# 6502_cable_ada.net
KiCad netlist of a schematic drawn in EAGLE
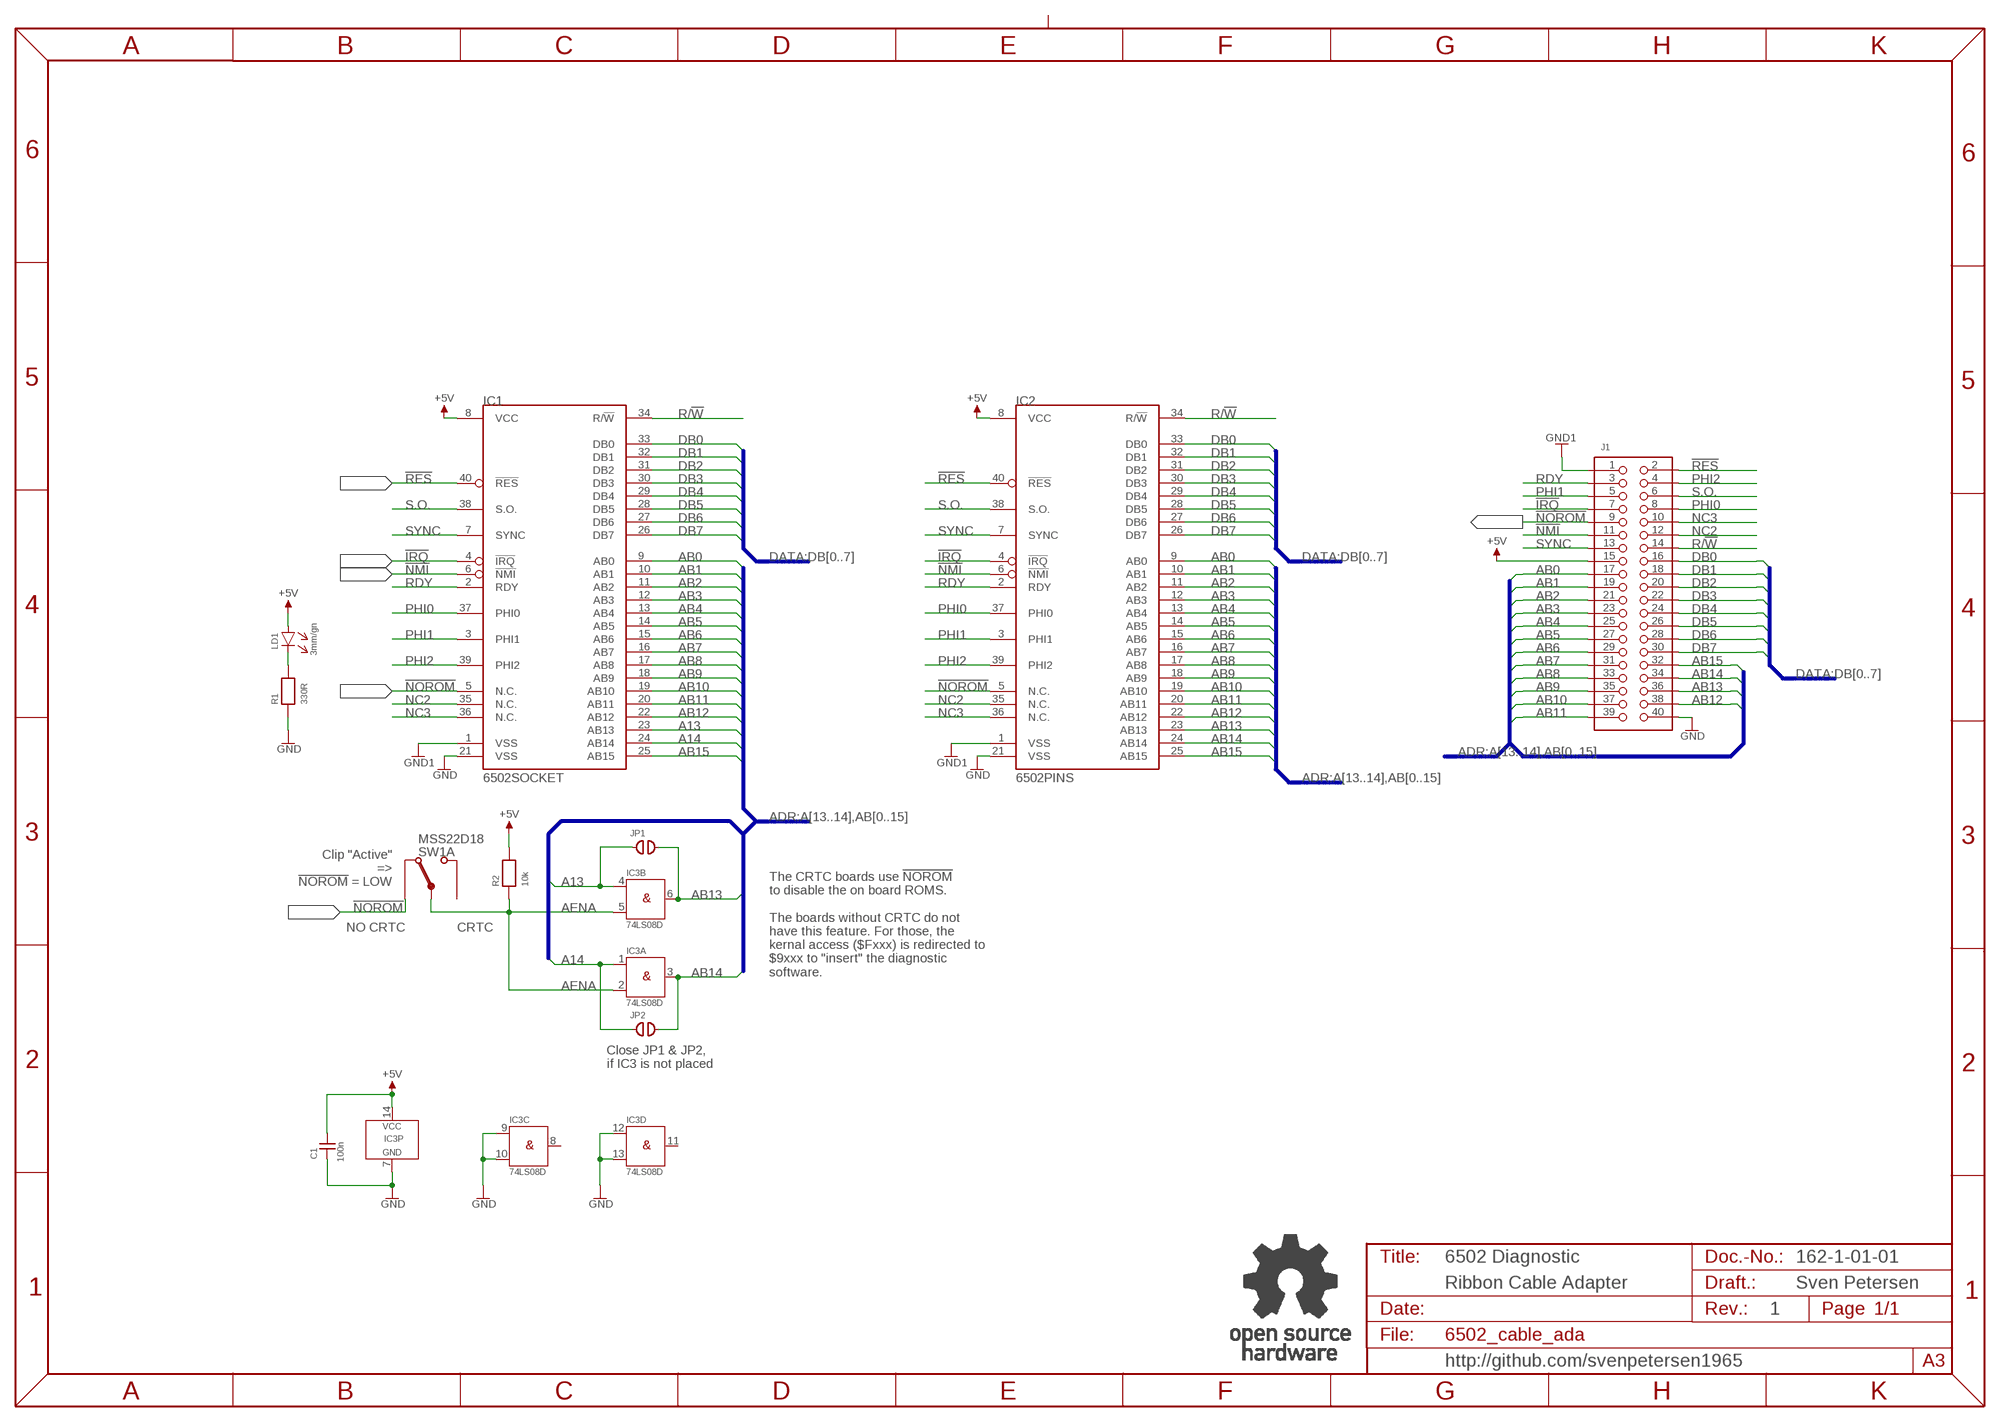
[diagram p0: schematic, sheet 1]

(export (version "E")
  (design (tool "Eeschema 10.0.6"))
  (components
    (comp (ref "C1")
      (value "100n")
      (footprint "eagle-import:0805")
      (libsource (lib "eagle-import") (part "C-0805"))
    )
    (comp (ref "IC1")
      (value "6502SOCKET")
      (footprint "eagle-import:GS40P")
      (libsource (lib "eagle-import") (part "6502SOCKET"))
    )
    (comp (ref "IC2")
      (value "6502PINS")
      (footprint "eagle-import:DIL40_PINS_SS")
      (libsource (lib "eagle-import") (part "6502PINS"))
    )
    (comp (ref "IC3")
      (value "74LS08D")
      (footprint "eagle-import:SO-14")
      (libsource (lib "eagle-import") (part "7408HC"))
    )
    (comp (ref "J1")
      (value "PINHD-2X20WV")
      (footprint "eagle-import:2X20WV")
      (libsource (lib "eagle-import") (part "PINHD-2X20WV"))
    )
    (comp (ref "JP1")
      (value "OPEN")
      (footprint "eagle-import:CP_OP")
      (libsource (lib "eagle-import") (part "OPEN"))
    )
    (comp (ref "JP2")
      (value "OPEN")
      (footprint "eagle-import:CP_OP")
      (libsource (lib "eagle-import") (part "OPEN"))
    )
    (comp (ref "LD1")
      (value "3mm/gn")
      (footprint "eagle-import:3MM")
      (libsource (lib "eagle-import") (part "3MM"))
    )
    (comp (ref "R1")
      (value "330R")
      (footprint "eagle-import:0805")
      (libsource (lib "eagle-import") (part "RES040805"))
    )
    (comp (ref "R2")
      (value "10k")
      (footprint "eagle-import:0805")
      (libsource (lib "eagle-import") (part "RES040805"))
    )
    (comp (ref "SW1")
      (value "MSS22D18")
      (footprint "eagle-import:DPDT_9MM")
      (libsource (lib "eagle-import") (part "DPDT_9MM"))
    )
    (comp (ref "U$11")
      (value "OPEN_SOURCE_HW")
      (footprint "eagle-import:OPENHW")
      (libsource (lib "eagle-import") (part "OPEN_SOURCE_HW"))
    )
  )
  (nets
    (net (code "9") (name "+5V") (class "Default")
      (node (ref "C1") (pin "2") (pinfunction "2_2") (pintype "passive"))
      (node (ref "IC1") (pin "8") (pinfunction "VCC_8") (pintype "power_in"))
      (node (ref "IC2") (pin "8") (pinfunction "VCC_8") (pintype "power_in"))
      (node (ref "IC3") (pin "14") (pinfunction "VCC_14") (pintype "bidirectional"))
      (node (ref "J1") (pin "15") (pinfunction "15_15") (pintype "passive"))
      (node (ref "LD1") (pin "A") (pinfunction "A_A") (pintype "bidirectional"))
      (node (ref "R2") (pin "2") (pinfunction "2_2") (pintype "passive"))
    )
    (net (code "10") (name "/A13") (class "Default")
      (node (ref "IC1") (pin "23") (pinfunction "AB13_23") (pintype "output"))
      (node (ref "IC3") (pin "4") (pinfunction "I0_4") (pintype "input"))
      (node (ref "JP1") (pin "1") (pinfunction "1_1") (pintype "passive"))
    )
    (net (code "11") (name "/A14") (class "Default")
      (node (ref "IC1") (pin "24") (pinfunction "AB14_24") (pintype "output"))
      (node (ref "IC3") (pin "1") (pinfunction "I0_1") (pintype "input"))
      (node (ref "JP2") (pin "1") (pinfunction "1_1") (pintype "passive"))
    )
    (net (code "12") (name "/AB0") (class "Default")
      (node (ref "IC1") (pin "9") (pinfunction "AB0_9") (pintype "output"))
      (node (ref "IC2") (pin "9") (pinfunction "AB0_9") (pintype "output"))
      (node (ref "J1") (pin "17") (pinfunction "17_17") (pintype "passive"))
    )
    (net (code "13") (name "/AB1") (class "Default")
      (node (ref "IC1") (pin "10") (pinfunction "AB1_10") (pintype "output"))
      (node (ref "IC2") (pin "10") (pinfunction "AB1_10") (pintype "output"))
      (node (ref "J1") (pin "19") (pinfunction "19_19") (pintype "passive"))
    )
    (net (code "14") (name "/AB2") (class "Default")
      (node (ref "IC1") (pin "11") (pinfunction "AB2_11") (pintype "output"))
      (node (ref "IC2") (pin "11") (pinfunction "AB2_11") (pintype "output"))
      (node (ref "J1") (pin "21") (pinfunction "21_21") (pintype "passive"))
    )
    (net (code "15") (name "/AB3") (class "Default")
      (node (ref "IC1") (pin "12") (pinfunction "AB3_12") (pintype "output"))
      (node (ref "IC2") (pin "12") (pinfunction "AB3_12") (pintype "output"))
      (node (ref "J1") (pin "23") (pinfunction "23_23") (pintype "passive"))
    )
    (net (code "16") (name "/AB4") (class "Default")
      (node (ref "IC1") (pin "13") (pinfunction "AB4_13") (pintype "output"))
      (node (ref "IC2") (pin "13") (pinfunction "AB4_13") (pintype "output"))
      (node (ref "J1") (pin "25") (pinfunction "25_25") (pintype "passive"))
    )
    (net (code "17") (name "/AB5") (class "Default")
      (node (ref "IC1") (pin "14") (pinfunction "AB5_14") (pintype "output"))
      (node (ref "IC2") (pin "14") (pinfunction "AB5_14") (pintype "output"))
      (node (ref "J1") (pin "27") (pinfunction "27_27") (pintype "passive"))
    )
    (net (code "18") (name "/AB6") (class "Default")
      (node (ref "IC1") (pin "15") (pinfunction "AB6_15") (pintype "output"))
      (node (ref "IC2") (pin "15") (pinfunction "AB6_15") (pintype "output"))
      (node (ref "J1") (pin "29") (pinfunction "29_29") (pintype "passive"))
    )
    (net (code "19") (name "/AB7") (class "Default")
      (node (ref "IC1") (pin "16") (pinfunction "AB7_16") (pintype "output"))
      (node (ref "IC2") (pin "16") (pinfunction "AB7_16") (pintype "output"))
      (node (ref "J1") (pin "31") (pinfunction "31_31") (pintype "passive"))
    )
    (net (code "20") (name "/AB8") (class "Default")
      (node (ref "IC1") (pin "17") (pinfunction "AB8_17") (pintype "output"))
      (node (ref "IC2") (pin "17") (pinfunction "AB8_17") (pintype "output"))
      (node (ref "J1") (pin "33") (pinfunction "33_33") (pintype "passive"))
    )
    (net (code "21") (name "/AB9") (class "Default")
      (node (ref "IC1") (pin "18") (pinfunction "AB9_18") (pintype "output"))
      (node (ref "IC2") (pin "18") (pinfunction "AB9_18") (pintype "output"))
      (node (ref "J1") (pin "35") (pinfunction "35_35") (pintype "passive"))
    )
    (net (code "22") (name "/AB10") (class "Default")
      (node (ref "IC1") (pin "19") (pinfunction "AB10_19") (pintype "output"))
      (node (ref "IC2") (pin "19") (pinfunction "AB10_19") (pintype "output"))
      (node (ref "J1") (pin "37") (pinfunction "37_37") (pintype "passive"))
    )
    (net (code "23") (name "/AB11") (class "Default")
      (node (ref "IC1") (pin "20") (pinfunction "AB11_20") (pintype "output"))
      (node (ref "IC2") (pin "20") (pinfunction "AB11_20") (pintype "output"))
      (node (ref "J1") (pin "39") (pinfunction "39_39") (pintype "passive"))
    )
    (net (code "24") (name "/AB12") (class "Default")
      (node (ref "IC1") (pin "22") (pinfunction "AB12_22") (pintype "output"))
      (node (ref "IC2") (pin "22") (pinfunction "AB12_22") (pintype "output"))
      (node (ref "J1") (pin "38") (pinfunction "38_38") (pintype "passive"))
    )
    (net (code "25") (name "/AB13") (class "Default")
      (node (ref "IC2") (pin "23") (pinfunction "AB13_23") (pintype "output"))
      (node (ref "IC3") (pin "6") (pinfunction "O_6") (pintype "output"))
      (node (ref "J1") (pin "36") (pinfunction "36_36") (pintype "passive"))
      (node (ref "JP1") (pin "2") (pinfunction "2_2") (pintype "passive"))
    )
    (net (code "26") (name "/AB14") (class "Default")
      (node (ref "IC2") (pin "24") (pinfunction "AB14_24") (pintype "output"))
      (node (ref "IC3") (pin "3") (pinfunction "O_3") (pintype "output"))
      (node (ref "J1") (pin "34") (pinfunction "34_34") (pintype "passive"))
      (node (ref "JP2") (pin "2") (pinfunction "2_2") (pintype "passive"))
    )
    (net (code "27") (name "/AB15") (class "Default")
      (node (ref "IC1") (pin "25") (pinfunction "AB15_25") (pintype "output"))
      (node (ref "IC2") (pin "25") (pinfunction "AB15_25") (pintype "output"))
      (node (ref "J1") (pin "32") (pinfunction "32_32") (pintype "passive"))
    )
    (net (code "28") (name "/AENA") (class "Default")
      (node (ref "IC3") (pin "2") (pinfunction "I1_2") (pintype "input"))
      (node (ref "IC3") (pin "5") (pinfunction "I1_5") (pintype "input"))
      (node (ref "R2") (pin "1") (pinfunction "1_1") (pintype "passive"))
      (node (ref "SW1") (pin "2") (pinfunction "COM_2") (pintype "bidirectional"))
    )
    (net (code "30") (name "/DB0") (class "Default")
      (node (ref "IC1") (pin "33") (pinfunction "DB0_33") (pintype "bidirectional"))
      (node (ref "IC2") (pin "33") (pinfunction "DB0_33") (pintype "bidirectional"))
      (node (ref "J1") (pin "16") (pinfunction "16_16") (pintype "passive"))
    )
    (net (code "31") (name "/DB1") (class "Default")
      (node (ref "IC1") (pin "32") (pinfunction "DB1_32") (pintype "bidirectional"))
      (node (ref "IC2") (pin "32") (pinfunction "DB1_32") (pintype "bidirectional"))
      (node (ref "J1") (pin "18") (pinfunction "18_18") (pintype "passive"))
    )
    (net (code "32") (name "/DB2") (class "Default")
      (node (ref "IC1") (pin "31") (pinfunction "DB2_31") (pintype "bidirectional"))
      (node (ref "IC2") (pin "31") (pinfunction "DB2_31") (pintype "bidirectional"))
      (node (ref "J1") (pin "20") (pinfunction "20_20") (pintype "passive"))
    )
    (net (code "33") (name "/DB3") (class "Default")
      (node (ref "IC1") (pin "30") (pinfunction "DB3_30") (pintype "bidirectional"))
      (node (ref "IC2") (pin "30") (pinfunction "DB3_30") (pintype "bidirectional"))
      (node (ref "J1") (pin "22") (pinfunction "22_22") (pintype "passive"))
    )
    (net (code "34") (name "/DB4") (class "Default")
      (node (ref "IC1") (pin "29") (pinfunction "DB4_29") (pintype "bidirectional"))
      (node (ref "IC2") (pin "29") (pinfunction "DB4_29") (pintype "bidirectional"))
      (node (ref "J1") (pin "24") (pinfunction "24_24") (pintype "passive"))
    )
    (net (code "35") (name "/DB5") (class "Default")
      (node (ref "IC1") (pin "28") (pinfunction "DB5_28") (pintype "bidirectional"))
      (node (ref "IC2") (pin "28") (pinfunction "DB5_28") (pintype "bidirectional"))
      (node (ref "J1") (pin "26") (pinfunction "26_26") (pintype "passive"))
    )
    (net (code "36") (name "/DB6") (class "Default")
      (node (ref "IC1") (pin "27") (pinfunction "DB6_27") (pintype "bidirectional"))
      (node (ref "IC2") (pin "27") (pinfunction "DB6_27") (pintype "bidirectional"))
      (node (ref "J1") (pin "28") (pinfunction "28_28") (pintype "passive"))
    )
    (net (code "37") (name "/DB7") (class "Default")
      (node (ref "IC1") (pin "26") (pinfunction "DB7_26") (pintype "bidirectional"))
      (node (ref "IC2") (pin "26") (pinfunction "DB7_26") (pintype "bidirectional"))
      (node (ref "J1") (pin "30") (pinfunction "30_30") (pintype "passive"))
    )
    (net (code "38") (name "/NC2") (class "Default")
      (node (ref "IC1") (pin "35") (pinfunction "N.C._35") (pintype "passive"))
      (node (ref "IC2") (pin "35") (pinfunction "N.C._35") (pintype "passive"))
      (node (ref "J1") (pin "12") (pinfunction "12_12") (pintype "passive"))
    )
    (net (code "39") (name "/NC3") (class "Default")
      (node (ref "IC1") (pin "36") (pinfunction "N.C._36") (pintype "passive"))
      (node (ref "IC2") (pin "36") (pinfunction "N.C._36") (pintype "passive"))
      (node (ref "J1") (pin "10") (pinfunction "10_10") (pintype "passive"))
    )
    (net (code "40") (name "/PHI0") (class "Default")
      (node (ref "IC1") (pin "37") (pinfunction "PHI0_37") (pintype "input"))
      (node (ref "IC2") (pin "37") (pinfunction "PHI0_37") (pintype "input"))
      (node (ref "J1") (pin "8") (pinfunction "8_8") (pintype "passive"))
    )
    (net (code "41") (name "/PHI1") (class "Default")
      (node (ref "IC1") (pin "3") (pinfunction "PHI1_3") (pintype "output"))
      (node (ref "IC2") (pin "3") (pinfunction "PHI1_3") (pintype "output"))
      (node (ref "J1") (pin "5") (pinfunction "5_5") (pintype "passive"))
    )
    (net (code "42") (name "/PHI2") (class "Default")
      (node (ref "IC1") (pin "39") (pinfunction "PHI2_39") (pintype "output"))
      (node (ref "IC2") (pin "39") (pinfunction "PHI2_39") (pintype "output"))
      (node (ref "J1") (pin "4") (pinfunction "4_4") (pintype "passive"))
    )
    (net (code "43") (name "/RDY") (class "Default")
      (node (ref "IC1") (pin "2") (pinfunction "RDY_2") (pintype "input"))
      (node (ref "IC2") (pin "2") (pinfunction "RDY_2") (pintype "input"))
      (node (ref "J1") (pin "3") (pinfunction "3_3") (pintype "passive"))
    )
    (net (code "44") (name "/R{slash}~{W}") (class "Default")
      (node (ref "IC1") (pin "34") (pinfunction "R/~{W}_34") (pintype "output"))
      (node (ref "IC2") (pin "34") (pinfunction "R/~{W}_34") (pintype "output"))
      (node (ref "J1") (pin "14") (pinfunction "14_14") (pintype "passive"))
    )
    (net (code "45") (name "/S.O.") (class "Default")
      (node (ref "IC1") (pin "38") (pinfunction "S.O._38") (pintype "input"))
      (node (ref "IC2") (pin "38") (pinfunction "S.O._38") (pintype "input"))
      (node (ref "J1") (pin "6") (pinfunction "6_6") (pintype "passive"))
    )
    (net (code "46") (name "/SYNC") (class "Default")
      (node (ref "IC1") (pin "7") (pinfunction "SYNC_7") (pintype "output"))
      (node (ref "IC2") (pin "7") (pinfunction "SYNC_7") (pintype "output"))
      (node (ref "J1") (pin "13") (pinfunction "13_13") (pintype "passive"))
    )
    (net (code "48") (name "/~{IRQ}") (class "Default")
      (node (ref "IC1") (pin "4") (pinfunction "~{IRQ}_4") (pintype "input"))
      (node (ref "IC2") (pin "4") (pinfunction "~{IRQ}_4") (pintype "input"))
      (node (ref "J1") (pin "7") (pinfunction "7_7") (pintype "passive"))
    )
    (net (code "49") (name "/~{NMI}") (class "Default")
      (node (ref "IC1") (pin "6") (pinfunction "~{NMI}_6") (pintype "input"))
      (node (ref "IC2") (pin "6") (pinfunction "~{NMI}_6") (pintype "input"))
      (node (ref "J1") (pin "11") (pinfunction "11_11") (pintype "passive"))
    )
    (net (code "50") (name "/~{NOROM}") (class "Default")
      (node (ref "IC1") (pin "5") (pinfunction "N.C._5") (pintype "passive"))
      (node (ref "IC2") (pin "5") (pinfunction "N.C._5") (pintype "passive"))
      (node (ref "J1") (pin "9") (pinfunction "9_9") (pintype "passive"))
      (node (ref "SW1") (pin "3") (pinfunction "DWN_3") (pintype "bidirectional"))
    )
    (net (code "51") (name "/~{RES}") (class "Default")
      (node (ref "IC1") (pin "40") (pinfunction "~{RES}_40") (pintype "input"))
      (node (ref "IC2") (pin "40") (pinfunction "~{RES}_40") (pintype "input"))
      (node (ref "J1") (pin "2") (pinfunction "2_2") (pintype "passive"))
    )
    (net (code "52") (name "GND") (class "Default")
      (node (ref "C1") (pin "1") (pinfunction "1_1") (pintype "passive"))
      (node (ref "IC1") (pin "21") (pinfunction "VSS_21") (pintype "power_in"))
      (node (ref "IC2") (pin "21") (pinfunction "VSS_21") (pintype "power_in"))
      (node (ref "IC3") (pin "10") (pinfunction "I1_10") (pintype "input"))
      (node (ref "IC3") (pin "12") (pinfunction "I0_12") (pintype "input"))
      (node (ref "IC3") (pin "13") (pinfunction "I1_13") (pintype "input"))
      (node (ref "IC3") (pin "7") (pinfunction "GND_7") (pintype "bidirectional"))
      (node (ref "IC3") (pin "9") (pinfunction "I0_9") (pintype "input"))
      (node (ref "J1") (pin "40") (pinfunction "40_40") (pintype "passive"))
      (node (ref "R1") (pin "1") (pinfunction "1_1") (pintype "passive"))
    )
    (net (code "53") (name "GND1") (class "Default")
      (node (ref "IC1") (pin "1") (pinfunction "VSS_1") (pintype "power_in"))
      (node (ref "IC2") (pin "1") (pinfunction "VSS_1") (pintype "power_in"))
      (node (ref "J1") (pin "1") (pinfunction "1_1") (pintype "passive"))
    )
    (net (code "54") (name "Net-(LD1-K)") (class "Default")
      (node (ref "LD1") (pin "C") (pinfunction "K_C") (pintype "bidirectional"))
      (node (ref "R1") (pin "2") (pinfunction "2_2") (pintype "passive"))
    )
    (net (code "55") (name "unconnected-(IC3C-O-Pad8)") (class "Default")
      (node (ref "IC3") (pin "8") (pinfunction "O_8") (pintype "output"))
    )
    (net (code "56") (name "unconnected-(IC3D-O-Pad11)") (class "Default")
      (node (ref "IC3") (pin "11") (pinfunction "O_11") (pintype "output"))
    )
    (net (code "57") (name "unconnected-(SW1A-UP-Pad1)") (class "Default")
      (node (ref "SW1") (pin "1") (pinfunction "UP_1") (pintype "bidirectional"))
    )
  )
)
